# m1-clock.net
KiCad netlist of a schematic drawn in EAGLE
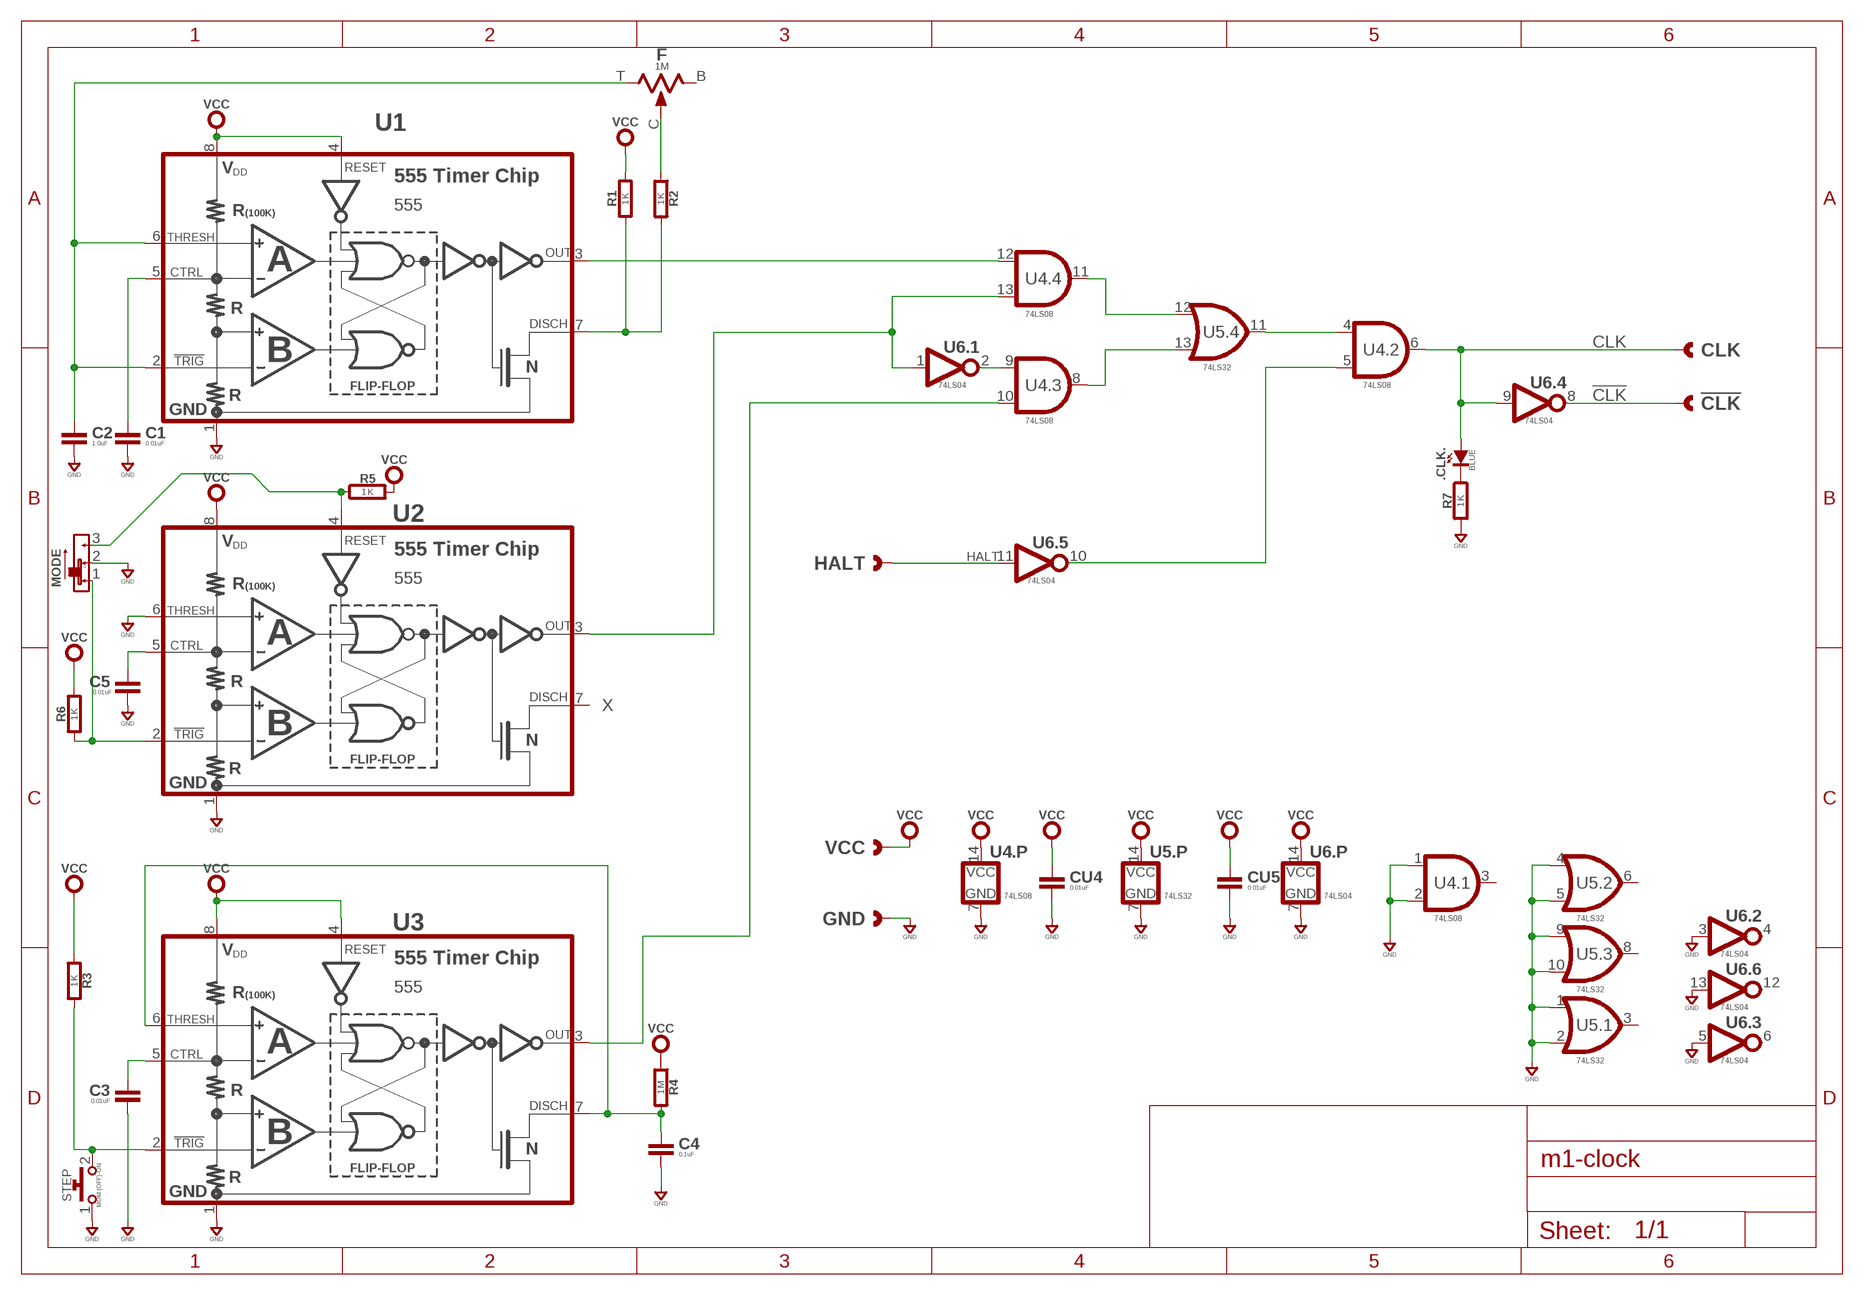
[diagram p0: schematic, sheet 1]

(export (version "E")
  (design (tool "Eeschema 10.0.6"))
  (components
    (comp (ref "!CLK")
      (value "CAST-01X1")
      (footprint "eagle-import:CAST01-2.54MM")
      (libsource (lib "eagle-import") (part "CAST-01X1"))
    )
    (comp (ref ".CLK.")
      (value "BLUE")
      (footprint "eagle-import:SMD_0603")
      (libsource (lib "eagle-import") (part "SMT0603"))
    )
    (comp (ref "C1")
      (value "0.01uF")
      (footprint "eagle-import:0603-CAP")
      (libsource (lib "eagle-import") (part "CAPACITOR0603"))
    )
    (comp (ref "C2")
      (value "1.0uF")
      (footprint "eagle-import:0603-CAP")
      (libsource (lib "eagle-import") (part "CAPACITOR0603"))
    )
    (comp (ref "C3")
      (value "0.01uF")
      (footprint "eagle-import:0603-CAP")
      (libsource (lib "eagle-import") (part "CAPACITOR0603"))
    )
    (comp (ref "C4")
      (value "0.1uF")
      (footprint "eagle-import:0603-CAP")
      (libsource (lib "eagle-import") (part "CAPACITOR0603"))
    )
    (comp (ref "C5")
      (value "0.01uF")
      (footprint "eagle-import:0603-CAP")
      (libsource (lib "eagle-import") (part "CAPACITOR0603"))
    )
    (comp (ref "CLK")
      (value "CAST-01X1")
      (footprint "eagle-import:CAST01-2.54MM")
      (libsource (lib "eagle-import") (part "CAST-01X1"))
    )
    (comp (ref "CU4")
      (value "0.01uF")
      (footprint "eagle-import:0603-CAP")
      (libsource (lib "eagle-import") (part "CAPACITOR0603"))
    )
    (comp (ref "CU5")
      (value "0.01uF")
      (footprint "eagle-import:0603-CAP")
      (libsource (lib "eagle-import") (part "CAPACITOR0603"))
    )
    (comp (ref "F")
      (value "1M")
      (footprint "eagle-import:TRIM_BOURNS_TC33X")
      (libsource (lib "eagle-import") (part "TRIMPOTTC33X"))
    )
    (comp (ref "GND")
      (value "CAST-01X1")
      (footprint "eagle-import:CAST01-2.54MM")
      (libsource (lib "eagle-import") (part "CAST-01X1"))
    )
    (comp (ref "HALT")
      (value "CAST-01X1")
      (footprint "eagle-import:CAST01-2.54MM")
      (libsource (lib "eagle-import") (part "CAST-01X1"))
    )
    (comp (ref "MODE")
      (value "SLIDE-SPDTJS102011JCQN")
      (footprint "eagle-import:CK_JS102011JCQN")
      (libsource (lib "eagle-import") (part "SLIDE-SPDTJS102011JCQN"))
    )
    (comp (ref "R1")
      (value "1K")
      (footprint "eagle-import:0603-RES")
      (libsource (lib "eagle-import") (part "RESISTOR0603"))
    )
    (comp (ref "R2")
      (value "1K")
      (footprint "eagle-import:0603-RES")
      (libsource (lib "eagle-import") (part "RESISTOR0603"))
    )
    (comp (ref "R3")
      (value "1K")
      (footprint "eagle-import:0603-RES")
      (libsource (lib "eagle-import") (part "RESISTOR0603"))
    )
    (comp (ref "R4")
      (value "1M")
      (footprint "eagle-import:0603-RES")
      (libsource (lib "eagle-import") (part "RESISTOR0603"))
    )
    (comp (ref "R5")
      (value "1K")
      (footprint "eagle-import:0603-RES")
      (libsource (lib "eagle-import") (part "RESISTOR0603"))
    )
    (comp (ref "R6")
      (value "1K")
      (footprint "eagle-import:0603-RES")
      (libsource (lib "eagle-import") (part "RESISTOR0603"))
    )
    (comp (ref "R7")
      (value "1K")
      (footprint "eagle-import:0603-RES")
      (libsource (lib "eagle-import") (part "RESISTOR0603"))
    )
    (comp (ref "STEP")
      (value "MOM (OFF)-ON")
      (footprint "eagle-import:SWITCH-0635-2P-SMD")
      (fields (field (name "MFR") "CK Switch") (field (name "MPN") "PTS635S*SMTR"))
      (libsource (lib "eagle-import") (part "TACTILE-2PSMD"))
    )
    (comp (ref "U1")
      (value "555")
      (footprint "eagle-import:SOP08")
      (fields (field (name "MFR") "TI") (field (name "MPN") "NE555PSR"))
      (libsource (lib "eagle-import") (part "555SOIC"))
    )
    (comp (ref "U2")
      (value "555")
      (footprint "eagle-import:SOP08")
      (fields (field (name "MFR") "TI") (field (name "MPN") "NE555PSR"))
      (libsource (lib "eagle-import") (part "555SOIC"))
    )
    (comp (ref "U3")
      (value "555")
      (footprint "eagle-import:SOP08")
      (fields (field (name "MFR") "TI") (field (name "MPN") "NE555PSR"))
      (libsource (lib "eagle-import") (part "555SOIC"))
    )
    (comp (ref "U4")
      (value "74LS08")
      (footprint "eagle-import:SOP14")
      (libsource (lib "eagle-import") (part "7408?DLS"))
    )
    (comp (ref "U5")
      (value "74LS32")
      (footprint "eagle-import:SOP14")
      (libsource (lib "eagle-import") (part "7432?DLS"))
    )
    (comp (ref "U6")
      (value "74LS04")
      (footprint "eagle-import:SOP14")
      (libsource (lib "eagle-import") (part "7404?DLS"))
    )
    (comp (ref "VCC")
      (value "CAST-01X1")
      (footprint "eagle-import:CAST01-2.54MM")
      (libsource (lib "eagle-import") (part "CAST-01X1"))
    )
  )
  (nets
    (net (code "1") (name "/CLK") (class "Default")
      (node (ref ".CLK.") (pin "A") (pinfunction "A_A") (pintype "passive"))
      (node (ref "CLK") (pin "1") (pinfunction "1_1") (pintype "bidirectional"))
      (node (ref "U4") (pin "6") (pinfunction "Y_6") (pintype "output"))
      (node (ref "U6") (pin "9") (pinfunction "A_9") (pintype "bidirectional"))
    )
    (net (code "2") (name "/HALT") (class "Default")
      (node (ref "HALT") (pin "1") (pinfunction "1_1") (pintype "bidirectional"))
      (node (ref "U6") (pin "11") (pinfunction "A_11") (pintype "bidirectional"))
    )
    (net (code "3") (name "/~{CLK}") (class "Default")
      (node (ref "!CLK") (pin "1") (pinfunction "1_1") (pintype "bidirectional"))
      (node (ref "U6") (pin "8") (pinfunction "Y_8") (pintype "bidirectional"))
    )
    (net (code "4") (name "GND") (class "Default")
      (node (ref "C1") (pin "2") (pinfunction "2_2") (pintype "passive"))
      (node (ref "C2") (pin "2") (pinfunction "2_2") (pintype "passive"))
      (node (ref "C3") (pin "2") (pinfunction "2_2") (pintype "passive"))
      (node (ref "C4") (pin "2") (pinfunction "2_2") (pintype "passive"))
      (node (ref "C5") (pin "2") (pinfunction "2_2") (pintype "passive"))
      (node (ref "CU4") (pin "2") (pinfunction "2_2") (pintype "passive"))
      (node (ref "CU5") (pin "2") (pinfunction "2_2") (pintype "passive"))
      (node (ref "GND") (pin "1") (pinfunction "1_1") (pintype "bidirectional"))
      (node (ref "MODE") (pin "2") (pinfunction "2_2") (pintype "bidirectional"))
      (node (ref "R7") (pin "2") (pinfunction "2_2") (pintype "passive"))
      (node (ref "STEP") (pin "1") (pinfunction "1_1") (pintype "bidirectional"))
      (node (ref "U1") (pin "1") (pinfunction "GND_1") (pintype "power_in"))
      (node (ref "U2") (pin "1") (pinfunction "GND_1") (pintype "power_in"))
      (node (ref "U2") (pin "6") (pinfunction "THRESHOLD_6") (pintype "input"))
      (node (ref "U3") (pin "1") (pinfunction "GND_1") (pintype "power_in"))
      (node (ref "U4") (pin "1") (pinfunction "A_1") (pintype "input"))
      (node (ref "U4") (pin "2") (pinfunction "B_2") (pintype "input"))
      (node (ref "U4") (pin "7") (pinfunction "GND_7") (pintype "power_in"))
      (node (ref "U5") (pin "1") (pinfunction "A_1") (pintype "input"))
      (node (ref "U5") (pin "10") (pinfunction "B_10") (pintype "input"))
      (node (ref "U5") (pin "2") (pinfunction "B_2") (pintype "input"))
      (node (ref "U5") (pin "4") (pinfunction "A_4") (pintype "input"))
      (node (ref "U5") (pin "5") (pinfunction "B_5") (pintype "input"))
      (node (ref "U5") (pin "7") (pinfunction "GND_7") (pintype "power_in"))
      (node (ref "U5") (pin "9") (pinfunction "A_9") (pintype "input"))
      (node (ref "U6") (pin "13") (pinfunction "A_13") (pintype "bidirectional"))
      (node (ref "U6") (pin "3") (pinfunction "A_3") (pintype "bidirectional"))
      (node (ref "U6") (pin "5") (pinfunction "A_5") (pintype "bidirectional"))
      (node (ref "U6") (pin "7") (pinfunction "GND_7") (pintype "power_in"))
    )
    (net (code "5") (name "Net-(.CLK.-C)") (class "Default")
      (node (ref ".CLK.") (pin "K") (pinfunction "C_K") (pintype "passive"))
      (node (ref "R7") (pin "1") (pinfunction "1_1") (pintype "passive"))
    )
    (net (code "6") (name "Net-(F-2)") (class "Default")
      (node (ref "F") (pin "C") (pinfunction "2_C") (pintype "passive"))
      (node (ref "R2") (pin "1") (pinfunction "1_1") (pintype "passive"))
    )
    (net (code "7") (name "Net-(F-3)") (class "Default")
      (node (ref "C2") (pin "1") (pinfunction "1_1") (pintype "passive"))
      (node (ref "F") (pin "T") (pinfunction "3_T") (pintype "passive"))
      (node (ref "U1") (pin "2") (pinfunction "TRIGGER#_2") (pintype "input"))
      (node (ref "U1") (pin "6") (pinfunction "THRESHOLD_6") (pintype "input"))
    )
    (net (code "8") (name "Net-(U1-CONTROL)") (class "Default")
      (node (ref "C1") (pin "1") (pinfunction "1_1") (pintype "passive"))
      (node (ref "U1") (pin "5") (pinfunction "CONTROL_5") (pintype "input"))
    )
    (net (code "9") (name "Net-(U1-DISCHARGE)") (class "Default")
      (node (ref "R1") (pin "1") (pinfunction "1_1") (pintype "passive"))
      (node (ref "R2") (pin "2") (pinfunction "2_2") (pintype "passive"))
      (node (ref "U1") (pin "7") (pinfunction "DISCHARGE_7") (pintype "output"))
    )
    (net (code "10") (name "Net-(U1-OUTPUT)") (class "Default")
      (node (ref "U1") (pin "3") (pinfunction "OUTPUT_3") (pintype "output"))
      (node (ref "U4") (pin "12") (pinfunction "A_12") (pintype "input"))
    )
    (net (code "11") (name "Net-(U2-CONTROL)") (class "Default")
      (node (ref "C5") (pin "1") (pinfunction "1_1") (pintype "passive"))
      (node (ref "U2") (pin "5") (pinfunction "CONTROL_5") (pintype "input"))
    )
    (net (code "12") (name "Net-(U2-OUTPUT)") (class "Default")
      (node (ref "U2") (pin "3") (pinfunction "OUTPUT_3") (pintype "output"))
      (node (ref "U4") (pin "13") (pinfunction "B_13") (pintype "input"))
      (node (ref "U6") (pin "1") (pinfunction "A_1") (pintype "bidirectional"))
    )
    (net (code "13") (name "Net-(U2-RESET#)") (class "Default")
      (node (ref "MODE") (pin "3") (pinfunction "3_3") (pintype "bidirectional"))
      (node (ref "R5") (pin "1") (pinfunction "1_1") (pintype "passive"))
      (node (ref "U2") (pin "4") (pinfunction "RESET#_4") (pintype "bidirectional"))
    )
    (net (code "14") (name "Net-(U2-TRIGGER#)") (class "Default")
      (node (ref "MODE") (pin "1") (pinfunction "1_1") (pintype "bidirectional"))
      (node (ref "R6") (pin "1") (pinfunction "1_1") (pintype "passive"))
      (node (ref "U2") (pin "2") (pinfunction "TRIGGER#_2") (pintype "input"))
    )
    (net (code "15") (name "Net-(U3-CONTROL)") (class "Default")
      (node (ref "C3") (pin "1") (pinfunction "1_1") (pintype "passive"))
      (node (ref "U3") (pin "5") (pinfunction "CONTROL_5") (pintype "input"))
    )
    (net (code "16") (name "Net-(U3-DISCHARGE)") (class "Default")
      (node (ref "C4") (pin "1") (pinfunction "1_1") (pintype "passive"))
      (node (ref "R4") (pin "2") (pinfunction "2_2") (pintype "passive"))
      (node (ref "U3") (pin "6") (pinfunction "THRESHOLD_6") (pintype "input"))
      (node (ref "U3") (pin "7") (pinfunction "DISCHARGE_7") (pintype "output"))
    )
    (net (code "17") (name "Net-(U3-OUTPUT)") (class "Default")
      (node (ref "U3") (pin "3") (pinfunction "OUTPUT_3") (pintype "output"))
      (node (ref "U4") (pin "10") (pinfunction "B_10") (pintype "input"))
    )
    (net (code "18") (name "Net-(U3-TRIGGER#)") (class "Default")
      (node (ref "R3") (pin "2") (pinfunction "2_2") (pintype "passive"))
      (node (ref "STEP") (pin "2") (pinfunction "2_2") (pintype "bidirectional"))
      (node (ref "U3") (pin "2") (pinfunction "TRIGGER#_2") (pintype "input"))
    )
    (net (code "19") (name "Net-(U4B-A)") (class "Default")
      (node (ref "U4") (pin "4") (pinfunction "A_4") (pintype "input"))
      (node (ref "U5") (pin "11") (pinfunction "Y_11") (pintype "output"))
    )
    (net (code "20") (name "Net-(U4B-B)") (class "Default")
      (node (ref "U4") (pin "5") (pinfunction "B_5") (pintype "input"))
      (node (ref "U6") (pin "10") (pinfunction "Y_10") (pintype "bidirectional"))
    )
    (net (code "21") (name "Net-(U4C-A)") (class "Default")
      (node (ref "U4") (pin "9") (pinfunction "A_9") (pintype "input"))
      (node (ref "U6") (pin "2") (pinfunction "Y_2") (pintype "bidirectional"))
    )
    (net (code "22") (name "Net-(U4C-Y)") (class "Default")
      (node (ref "U4") (pin "8") (pinfunction "Y_8") (pintype "output"))
      (node (ref "U5") (pin "13") (pinfunction "B_13") (pintype "input"))
    )
    (net (code "23") (name "Net-(U4D-Y)") (class "Default")
      (node (ref "U4") (pin "11") (pinfunction "Y_11") (pintype "output"))
      (node (ref "U5") (pin "12") (pinfunction "A_12") (pintype "input"))
    )
    (net (code "24") (name "VCC") (class "Default")
      (node (ref "CU4") (pin "1") (pinfunction "1_1") (pintype "passive"))
      (node (ref "CU5") (pin "1") (pinfunction "1_1") (pintype "passive"))
      (node (ref "R1") (pin "2") (pinfunction "2_2") (pintype "passive"))
      (node (ref "R3") (pin "1") (pinfunction "1_1") (pintype "passive"))
      (node (ref "R4") (pin "1") (pinfunction "1_1") (pintype "passive"))
      (node (ref "R5") (pin "2") (pinfunction "2_2") (pintype "passive"))
      (node (ref "R6") (pin "2") (pinfunction "2_2") (pintype "passive"))
      (node (ref "U1") (pin "4") (pinfunction "RESET#_4") (pintype "bidirectional"))
      (node (ref "U1") (pin "8") (pinfunction "VDD_8") (pintype "power_in"))
      (node (ref "U2") (pin "8") (pinfunction "VDD_8") (pintype "power_in"))
      (node (ref "U3") (pin "4") (pinfunction "RESET#_4") (pintype "bidirectional"))
      (node (ref "U3") (pin "8") (pinfunction "VDD_8") (pintype "power_in"))
      (node (ref "U4") (pin "14") (pinfunction "VCC_14") (pintype "power_in"))
      (node (ref "U5") (pin "14") (pinfunction "VCC_14") (pintype "power_in"))
      (node (ref "U6") (pin "14") (pinfunction "VCC_14") (pintype "power_in"))
      (node (ref "VCC") (pin "1") (pinfunction "1_1") (pintype "bidirectional"))
    )
    (net (code "25") (name "unconnected-(F-1-PadB)") (class "Default")
      (node (ref "F") (pin "B") (pinfunction "1_B") (pintype "passive"))
    )
    (net (code "26") (name "unconnected-(U2-DISCHARGE-Pad7)") (class "Default")
      (node (ref "U2") (pin "7") (pinfunction "DISCHARGE_7") (pintype "output"))
    )
    (net (code "27") (name "unconnected-(U4A-Y-Pad3)") (class "Default")
      (node (ref "U4") (pin "3") (pinfunction "Y_3") (pintype "output"))
    )
    (net (code "28") (name "unconnected-(U5A-Y-Pad3)") (class "Default")
      (node (ref "U5") (pin "3") (pinfunction "Y_3") (pintype "output"))
    )
    (net (code "29") (name "unconnected-(U5B-Y-Pad6)") (class "Default")
      (node (ref "U5") (pin "6") (pinfunction "Y_6") (pintype "output"))
    )
    (net (code "30") (name "unconnected-(U5C-Y-Pad8)") (class "Default")
      (node (ref "U5") (pin "8") (pinfunction "Y_8") (pintype "output"))
    )
    (net (code "31") (name "unconnected-(U6B-Y-Pad4)") (class "Default")
      (node (ref "U6") (pin "4") (pinfunction "Y_4") (pintype "bidirectional"))
    )
    (net (code "32") (name "unconnected-(U6C-Y-Pad6)") (class "Default")
      (node (ref "U6") (pin "6") (pinfunction "Y_6") (pintype "bidirectional"))
    )
    (net (code "33") (name "unconnected-(U6F-Y-Pad12)") (class "Default")
      (node (ref "U6") (pin "12") (pinfunction "Y_12") (pintype "bidirectional"))
    )
  )
)
